# The_Lights.net
KiCad netlist of a schematic drawn in Altium Designer
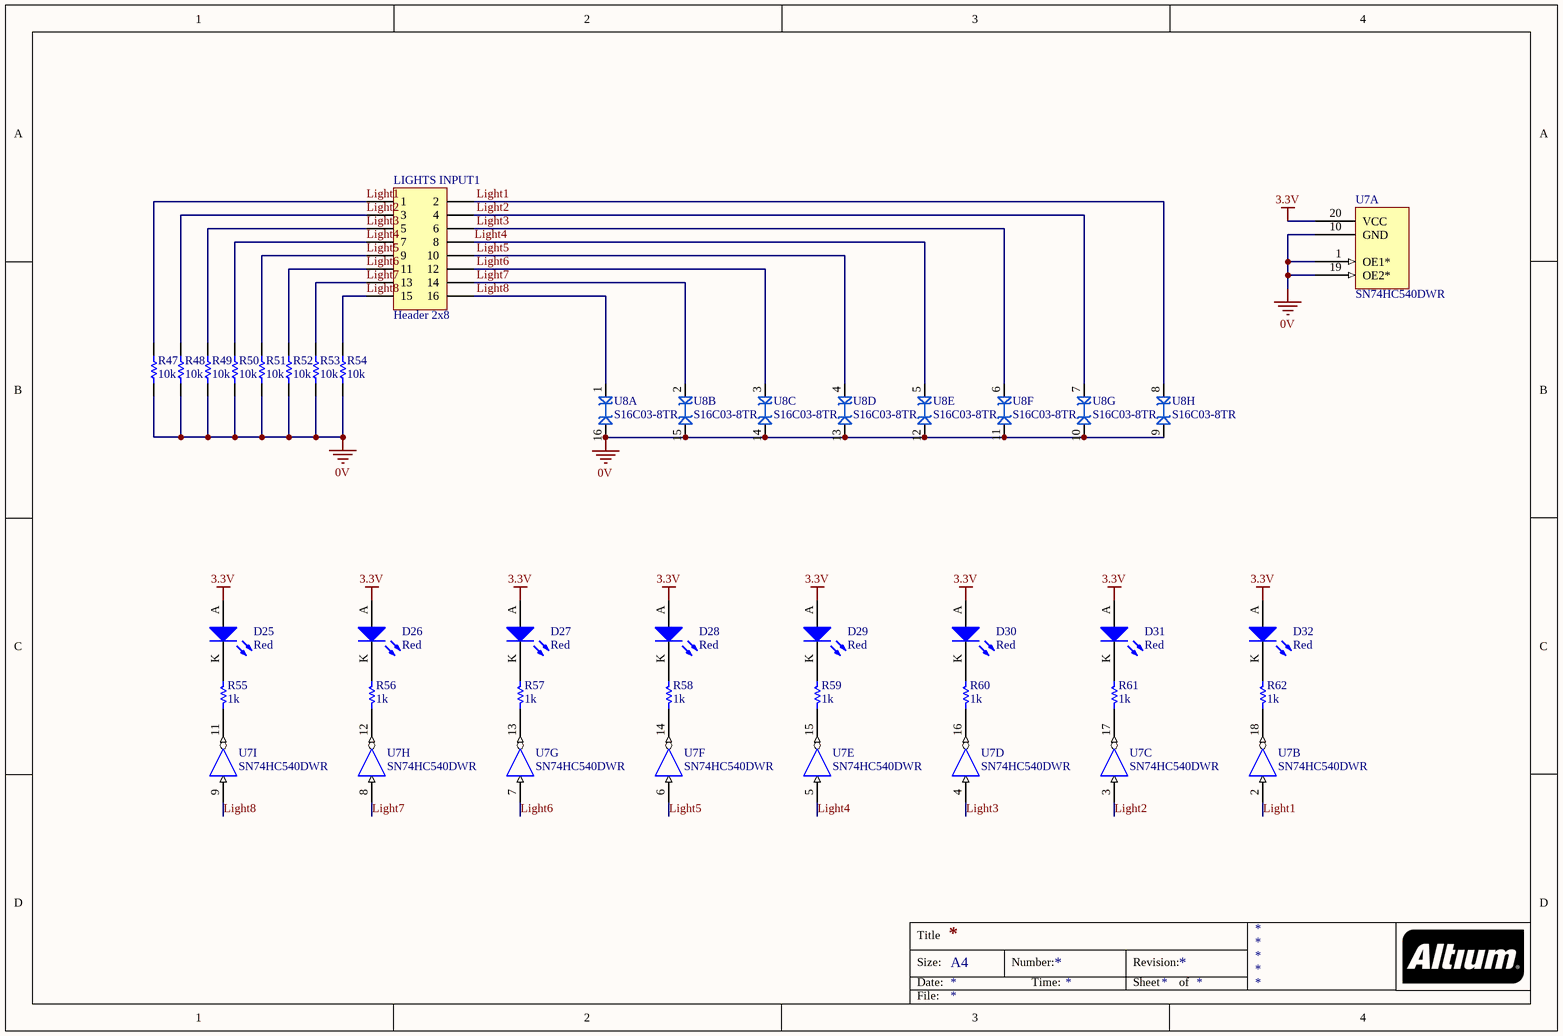
[diagram p0: The Lights.SchDoc]

(export (version "E")
  (design (tool "Eeschema 10.0.6"))
  (components
    (comp (ref "D25")
      (value "Red")
      (footprint "0805 LED")
      (description "Red LED Indication - Discrete 1.75V 0805 (2012 Metric)")
      (fields (field (name "MANUFACTURER") "ROHM Semiconductor") (field (name "PART NUMBER") "SML-210LTT86"))
      (libsource (lib "ts_19-standard-library") (part "LED"))
    )
    (comp (ref "D26")
      (value "Red")
      (footprint "0805 LED")
      (description "Red LED Indication - Discrete 1.75V 0805 (2012 Metric)")
      (fields (field (name "MANUFACTURER") "ROHM Semiconductor") (field (name "PART NUMBER") "SML-210LTT86"))
      (libsource (lib "ts_19-standard-library") (part "LED"))
    )
    (comp (ref "D27")
      (value "Red")
      (footprint "0805 LED")
      (description "Red LED Indication - Discrete 1.75V 0805 (2012 Metric)")
      (fields (field (name "MANUFACTURER") "ROHM Semiconductor") (field (name "PART NUMBER") "SML-210LTT86"))
      (libsource (lib "ts_19-standard-library") (part "LED"))
    )
    (comp (ref "D28")
      (value "Red")
      (footprint "0805 LED")
      (description "Red LED Indication - Discrete 1.75V 0805 (2012 Metric)")
      (fields (field (name "MANUFACTURER") "ROHM Semiconductor") (field (name "PART NUMBER") "SML-210LTT86"))
      (libsource (lib "ts_19-standard-library") (part "LED"))
    )
    (comp (ref "D29")
      (value "Red")
      (footprint "0805 LED")
      (description "Red LED Indication - Discrete 1.75V 0805 (2012 Metric)")
      (fields (field (name "MANUFACTURER") "ROHM Semiconductor") (field (name "PART NUMBER") "SML-210LTT86"))
      (libsource (lib "ts_19-standard-library") (part "LED"))
    )
    (comp (ref "D30")
      (value "Red")
      (footprint "0805 LED")
      (description "Red LED Indication - Discrete 1.75V 0805 (2012 Metric)")
      (fields (field (name "MANUFACTURER") "ROHM Semiconductor") (field (name "PART NUMBER") "SML-210LTT86"))
      (libsource (lib "ts_19-standard-library") (part "LED"))
    )
    (comp (ref "D31")
      (value "Red")
      (footprint "0805 LED")
      (description "Red LED Indication - Discrete 1.75V 0805 (2012 Metric)")
      (fields (field (name "MANUFACTURER") "ROHM Semiconductor") (field (name "PART NUMBER") "SML-210LTT86"))
      (libsource (lib "ts_19-standard-library") (part "LED"))
    )
    (comp (ref "D32")
      (value "Red")
      (footprint "0805 LED")
      (description "Red LED Indication - Discrete 1.75V 0805 (2012 Metric)")
      (fields (field (name "MANUFACTURER") "ROHM Semiconductor") (field (name "PART NUMBER") "SML-210LTT86"))
      (libsource (lib "ts_19-standard-library") (part "LED"))
    )
    (comp (ref "LIGHTS INPUT1")
      (value "Header 2x8")
      (footprint "Header 2x8")
      (fields (field (name "CONTACT") "NA"))
      (libsource (lib "ts_19-standard-connectors-IED") (part "Header 2x8"))
    )
    (comp (ref "R47")
      (value "10k")
      (footprint "0805")
      (fields
        (field (name "MANUFACTURER") "YAGEO")
        (field (name "PART NUMBER") "RC0805FR0710KL")
        (field (name "TOLERANCE") "0.01")
      )
      (libsource (lib "ts_19-standard-library-IED") (part "Resistor"))
    )
    (comp (ref "R48")
      (value "10k")
      (footprint "0805")
      (fields
        (field (name "MANUFACTURER") "YAGEO")
        (field (name "PART NUMBER") "RC0805FR0710KL")
        (field (name "TOLERANCE") "0.01")
      )
      (libsource (lib "ts_19-standard-library-IED") (part "Resistor"))
    )
    (comp (ref "R49")
      (value "10k")
      (footprint "0805")
      (fields
        (field (name "MANUFACTURER") "YAGEO")
        (field (name "PART NUMBER") "RC0805FR0710KL")
        (field (name "TOLERANCE") "0.01")
      )
      (libsource (lib "ts_19-standard-library-IED") (part "Resistor"))
    )
    (comp (ref "R50")
      (value "10k")
      (footprint "0805")
      (fields
        (field (name "MANUFACTURER") "YAGEO")
        (field (name "PART NUMBER") "RC0805FR0710KL")
        (field (name "TOLERANCE") "0.01")
      )
      (libsource (lib "ts_19-standard-library-IED") (part "Resistor"))
    )
    (comp (ref "R51")
      (value "10k")
      (footprint "0805")
      (fields
        (field (name "MANUFACTURER") "YAGEO")
        (field (name "PART NUMBER") "RC0805FR0710KL")
        (field (name "TOLERANCE") "0.01")
      )
      (libsource (lib "ts_19-standard-library-IED") (part "Resistor"))
    )
    (comp (ref "R52")
      (value "10k")
      (footprint "0805")
      (fields
        (field (name "MANUFACTURER") "YAGEO")
        (field (name "PART NUMBER") "RC0805FR0710KL")
        (field (name "TOLERANCE") "0.01")
      )
      (libsource (lib "ts_19-standard-library-IED") (part "Resistor"))
    )
    (comp (ref "R53")
      (value "10k")
      (footprint "0805")
      (fields
        (field (name "MANUFACTURER") "YAGEO")
        (field (name "PART NUMBER") "RC0805FR0710KL")
        (field (name "TOLERANCE") "0.01")
      )
      (libsource (lib "ts_19-standard-library-IED") (part "Resistor"))
    )
    (comp (ref "R54")
      (value "10k")
      (footprint "0805")
      (fields
        (field (name "MANUFACTURER") "YAGEO")
        (field (name "PART NUMBER") "RC0805FR0710KL")
        (field (name "TOLERANCE") "0.01")
      )
      (libsource (lib "ts_19-standard-library-IED") (part "Resistor"))
    )
    (comp (ref "R55")
      (value "1k")
      (footprint "0805")
      (fields
        (field (name "MANUFACTURER") "YAGEO")
        (field (name "PART NUMBER") "RC0805FR071KL")
        (field (name "TOLERANCE") "0.01")
      )
      (libsource (lib "ts_19-standard-library-IED") (part "Resistor"))
    )
    (comp (ref "R56")
      (value "1k")
      (footprint "0805")
      (fields
        (field (name "MANUFACTURER") "YAGEO")
        (field (name "PART NUMBER") "RC0805FR071KL")
        (field (name "TOLERANCE") "0.01")
      )
      (libsource (lib "ts_19-standard-library-IED") (part "Resistor"))
    )
    (comp (ref "R57")
      (value "1k")
      (footprint "0805")
      (fields
        (field (name "MANUFACTURER") "YAGEO")
        (field (name "PART NUMBER") "RC0805FR071KL")
        (field (name "TOLERANCE") "0.01")
      )
      (libsource (lib "ts_19-standard-library-IED") (part "Resistor"))
    )
    (comp (ref "R58")
      (value "1k")
      (footprint "0805")
      (fields
        (field (name "MANUFACTURER") "YAGEO")
        (field (name "PART NUMBER") "RC0805FR071KL")
        (field (name "TOLERANCE") "0.01")
      )
      (libsource (lib "ts_19-standard-library-IED") (part "Resistor"))
    )
    (comp (ref "R59")
      (value "1k")
      (footprint "0805")
      (fields
        (field (name "MANUFACTURER") "YAGEO")
        (field (name "PART NUMBER") "RC0805FR071KL")
        (field (name "TOLERANCE") "0.01")
      )
      (libsource (lib "ts_19-standard-library-IED") (part "Resistor"))
    )
    (comp (ref "R60")
      (value "1k")
      (footprint "0805")
      (fields
        (field (name "MANUFACTURER") "YAGEO")
        (field (name "PART NUMBER") "RC0805FR071KL")
        (field (name "TOLERANCE") "0.01")
      )
      (libsource (lib "ts_19-standard-library-IED") (part "Resistor"))
    )
    (comp (ref "R61")
      (value "1k")
      (footprint "0805")
      (fields
        (field (name "MANUFACTURER") "YAGEO")
        (field (name "PART NUMBER") "RC0805FR071KL")
        (field (name "TOLERANCE") "0.01")
      )
      (libsource (lib "ts_19-standard-library-IED") (part "Resistor"))
    )
    (comp (ref "R62")
      (value "1k")
      (footprint "0805")
      (fields
        (field (name "MANUFACTURER") "YAGEO")
        (field (name "PART NUMBER") "RC0805FR071KL")
        (field (name "TOLERANCE") "0.01")
      )
      (libsource (lib "ts_19-standard-library-IED") (part "Resistor"))
    )
    (comp (ref "U7")
      (value "SN74HC540DWR")
      (footprint "TI 20-SOIC")
      (description "IC BUFFER INVERT 6V 20SOIC")
      (fields
        (field (name "MANUFACTURER") "Texas Instruments")
        (field (name "DIGIKEY PART NUMBER") "296-8333-1-ND")
      )
      (libsource (lib "ts_19-standard-library") (part "SN74HC540DWR"))
    )
    (comp (ref "U8")
      (value "S16C03-8TR")
      (footprint "SMC 16-SOIC")
      (description "PD 300W VWM 3.3VCJ 425PFPACKAGE")
      (fields (field (name "MANUFACTURER") "SMC Diode") (field (name "DIGIKEY PART NUMBER") "1655-2152-2-ND"))
      (libsource (lib "ts_19-standard-library-IED") (part "S16C03-8TR"))
    )
  )
  (nets
    (net (code "1") (name "/Light1") (class "Default")
      (node (ref "LIGHTS INPUT1") (pin "1") (pinfunction "1_1") (pintype "passive"))
      (node (ref "LIGHTS INPUT1") (pin "2") (pinfunction "2_2") (pintype "passive"))
      (node (ref "R47") (pin "2") (pinfunction "2_2") (pintype "passive"))
      (node (ref "U7") (pin "2") (pinfunction "A1_2") (pintype "input"))
      (node (ref "U8") (pin "8") (pinfunction "A_8") (pintype "passive"))
    )
    (net (code "2") (name "/Light2") (class "Default")
      (node (ref "LIGHTS INPUT1") (pin "3") (pinfunction "3_3") (pintype "passive"))
      (node (ref "LIGHTS INPUT1") (pin "4") (pinfunction "4_4") (pintype "passive"))
      (node (ref "R48") (pin "2") (pinfunction "2_2") (pintype "passive"))
      (node (ref "U7") (pin "3") (pinfunction "A2_3") (pintype "input"))
      (node (ref "U8") (pin "7") (pinfunction "A_7") (pintype "passive"))
    )
    (net (code "3") (name "/Light3") (class "Default")
      (node (ref "LIGHTS INPUT1") (pin "5") (pinfunction "5_5") (pintype "passive"))
      (node (ref "LIGHTS INPUT1") (pin "6") (pinfunction "6_6") (pintype "passive"))
      (node (ref "R49") (pin "2") (pinfunction "2_2") (pintype "passive"))
      (node (ref "U7") (pin "4") (pinfunction "A3_4") (pintype "input"))
      (node (ref "U8") (pin "6") (pinfunction "A_6") (pintype "passive"))
    )
    (net (code "4") (name "/Light4") (class "Default")
      (node (ref "LIGHTS INPUT1") (pin "7") (pinfunction "7_7") (pintype "passive"))
      (node (ref "LIGHTS INPUT1") (pin "8") (pinfunction "8_8") (pintype "passive"))
      (node (ref "R50") (pin "2") (pinfunction "2_2") (pintype "passive"))
      (node (ref "U7") (pin "5") (pinfunction "A4_5") (pintype "input"))
      (node (ref "U8") (pin "5") (pinfunction "A_5") (pintype "passive"))
    )
    (net (code "5") (name "/Light5") (class "Default")
      (node (ref "LIGHTS INPUT1") (pin "10") (pinfunction "10_10") (pintype "passive"))
      (node (ref "LIGHTS INPUT1") (pin "9") (pinfunction "9_9") (pintype "passive"))
      (node (ref "R51") (pin "2") (pinfunction "2_2") (pintype "passive"))
      (node (ref "U7") (pin "6") (pinfunction "A5_6") (pintype "input"))
      (node (ref "U8") (pin "4") (pinfunction "A_4") (pintype "passive"))
    )
    (net (code "6") (name "/Light6") (class "Default")
      (node (ref "LIGHTS INPUT1") (pin "11") (pinfunction "11_11") (pintype "passive"))
      (node (ref "LIGHTS INPUT1") (pin "12") (pinfunction "12_12") (pintype "passive"))
      (node (ref "R52") (pin "2") (pinfunction "2_2") (pintype "passive"))
      (node (ref "U7") (pin "7") (pinfunction "A6_7") (pintype "input"))
      (node (ref "U8") (pin "3") (pinfunction "A_3") (pintype "passive"))
    )
    (net (code "7") (name "/Light7") (class "Default")
      (node (ref "LIGHTS INPUT1") (pin "13") (pinfunction "13_13") (pintype "passive"))
      (node (ref "LIGHTS INPUT1") (pin "14") (pinfunction "14_14") (pintype "passive"))
      (node (ref "R53") (pin "2") (pinfunction "2_2") (pintype "passive"))
      (node (ref "U7") (pin "8") (pinfunction "A7_8") (pintype "input"))
      (node (ref "U8") (pin "2") (pinfunction "A_2") (pintype "passive"))
    )
    (net (code "8") (name "/Light8") (class "Default")
      (node (ref "LIGHTS INPUT1") (pin "15") (pinfunction "15_15") (pintype "passive"))
      (node (ref "LIGHTS INPUT1") (pin "16") (pinfunction "16_16") (pintype "passive"))
      (node (ref "R54") (pin "2") (pinfunction "2_2") (pintype "passive"))
      (node (ref "U7") (pin "9") (pinfunction "A8_9") (pintype "input"))
      (node (ref "U8") (pin "1") (pinfunction "A_1") (pintype "passive"))
    )
    (net (code "9") (name "0V") (class "Default")
      (node (ref "R47") (pin "1") (pinfunction "1_1") (pintype "passive"))
      (node (ref "R48") (pin "1") (pinfunction "1_1") (pintype "passive"))
      (node (ref "R49") (pin "1") (pinfunction "1_1") (pintype "passive"))
      (node (ref "R50") (pin "1") (pinfunction "1_1") (pintype "passive"))
      (node (ref "R51") (pin "1") (pinfunction "1_1") (pintype "passive"))
      (node (ref "R52") (pin "1") (pinfunction "1_1") (pintype "passive"))
      (node (ref "R53") (pin "1") (pinfunction "1_1") (pintype "passive"))
      (node (ref "R54") (pin "1") (pinfunction "1_1") (pintype "passive"))
      (node (ref "U7") (pin "1") (pinfunction "OE1*_1") (pintype "input"))
      (node (ref "U7") (pin "10") (pinfunction "GND_10") (pintype "power_in"))
      (node (ref "U7") (pin "19") (pinfunction "OE2*_19") (pintype "input"))
      (node (ref "U8") (pin "10") (pinfunction "A_10") (pintype "passive"))
      (node (ref "U8") (pin "11") (pinfunction "A_11") (pintype "passive"))
      (node (ref "U8") (pin "12") (pinfunction "A_12") (pintype "passive"))
      (node (ref "U8") (pin "13") (pinfunction "A_13") (pintype "passive"))
      (node (ref "U8") (pin "14") (pinfunction "A_14") (pintype "passive"))
      (node (ref "U8") (pin "15") (pinfunction "A_15") (pintype "passive"))
      (node (ref "U8") (pin "16") (pinfunction "A_16") (pintype "passive"))
      (node (ref "U8") (pin "9") (pinfunction "A_9") (pintype "passive"))
    )
    (net (code "10") (name "3.3V") (class "Default")
      (node (ref "D25") (pin "A") (pinfunction "A_A") (pintype "passive"))
      (node (ref "D26") (pin "A") (pinfunction "A_A") (pintype "passive"))
      (node (ref "D27") (pin "A") (pinfunction "A_A") (pintype "passive"))
      (node (ref "D28") (pin "A") (pinfunction "A_A") (pintype "passive"))
      (node (ref "D29") (pin "A") (pinfunction "A_A") (pintype "passive"))
      (node (ref "D30") (pin "A") (pinfunction "A_A") (pintype "passive"))
      (node (ref "D31") (pin "A") (pinfunction "A_A") (pintype "passive"))
      (node (ref "D32") (pin "A") (pinfunction "A_A") (pintype "passive"))
      (node (ref "U7") (pin "20") (pinfunction "VCC_20") (pintype "power_in"))
    )
    (net (code "11") (name "Net-(D25-PadK)") (class "Default")
      (node (ref "D25") (pin "K") (pinfunction "K_K") (pintype "passive"))
      (node (ref "R55") (pin "1") (pinfunction "1_1") (pintype "passive"))
    )
    (net (code "12") (name "Net-(D26-PadK)") (class "Default")
      (node (ref "D26") (pin "K") (pinfunction "K_K") (pintype "passive"))
      (node (ref "R56") (pin "1") (pinfunction "1_1") (pintype "passive"))
    )
    (net (code "13") (name "Net-(D27-PadK)") (class "Default")
      (node (ref "D27") (pin "K") (pinfunction "K_K") (pintype "passive"))
      (node (ref "R57") (pin "1") (pinfunction "1_1") (pintype "passive"))
    )
    (net (code "14") (name "Net-(D28-PadK)") (class "Default")
      (node (ref "D28") (pin "K") (pinfunction "K_K") (pintype "passive"))
      (node (ref "R58") (pin "1") (pinfunction "1_1") (pintype "passive"))
    )
    (net (code "15") (name "Net-(D29-PadK)") (class "Default")
      (node (ref "D29") (pin "K") (pinfunction "K_K") (pintype "passive"))
      (node (ref "R59") (pin "1") (pinfunction "1_1") (pintype "passive"))
    )
    (net (code "16") (name "Net-(D30-PadK)") (class "Default")
      (node (ref "D30") (pin "K") (pinfunction "K_K") (pintype "passive"))
      (node (ref "R60") (pin "1") (pinfunction "1_1") (pintype "passive"))
    )
    (net (code "17") (name "Net-(D31-PadK)") (class "Default")
      (node (ref "D31") (pin "K") (pinfunction "K_K") (pintype "passive"))
      (node (ref "R61") (pin "1") (pinfunction "1_1") (pintype "passive"))
    )
    (net (code "18") (name "Net-(D32-PadK)") (class "Default")
      (node (ref "D32") (pin "K") (pinfunction "K_K") (pintype "passive"))
      (node (ref "R62") (pin "1") (pinfunction "1_1") (pintype "passive"))
    )
    (net (code "19") (name "Net-(U7B-Y1)") (class "Default")
      (node (ref "R62") (pin "2") (pinfunction "2_2") (pintype "passive"))
      (node (ref "U7") (pin "18") (pinfunction "Y1_18") (pintype "output"))
    )
    (net (code "20") (name "Net-(U7C-Y2)") (class "Default")
      (node (ref "R61") (pin "2") (pinfunction "2_2") (pintype "passive"))
      (node (ref "U7") (pin "17") (pinfunction "Y2_17") (pintype "output"))
    )
    (net (code "21") (name "Net-(U7D-Y3)") (class "Default")
      (node (ref "R60") (pin "2") (pinfunction "2_2") (pintype "passive"))
      (node (ref "U7") (pin "16") (pinfunction "Y3_16") (pintype "output"))
    )
    (net (code "22") (name "Net-(U7E-Y5)") (class "Default")
      (node (ref "R59") (pin "2") (pinfunction "2_2") (pintype "passive"))
      (node (ref "U7") (pin "15") (pinfunction "Y5_15") (pintype "output"))
    )
    (net (code "23") (name "Net-(U7F-Y5)") (class "Default")
      (node (ref "R58") (pin "2") (pinfunction "2_2") (pintype "passive"))
      (node (ref "U7") (pin "14") (pinfunction "Y5_14") (pintype "output"))
    )
    (net (code "24") (name "Net-(U7G-Y6)") (class "Default")
      (node (ref "R57") (pin "2") (pinfunction "2_2") (pintype "passive"))
      (node (ref "U7") (pin "13") (pinfunction "Y6_13") (pintype "output"))
    )
    (net (code "25") (name "Net-(U7H-Y7)") (class "Default")
      (node (ref "R56") (pin "2") (pinfunction "2_2") (pintype "passive"))
      (node (ref "U7") (pin "12") (pinfunction "Y7_12") (pintype "output"))
    )
    (net (code "26") (name "Net-(U7I-Y8)") (class "Default")
      (node (ref "R55") (pin "2") (pinfunction "2_2") (pintype "passive"))
      (node (ref "U7") (pin "11") (pinfunction "Y8_11") (pintype "output"))
    )
  )
)
